# electronicload.net
KiCad netlist of a schematic drawn in EAGLE
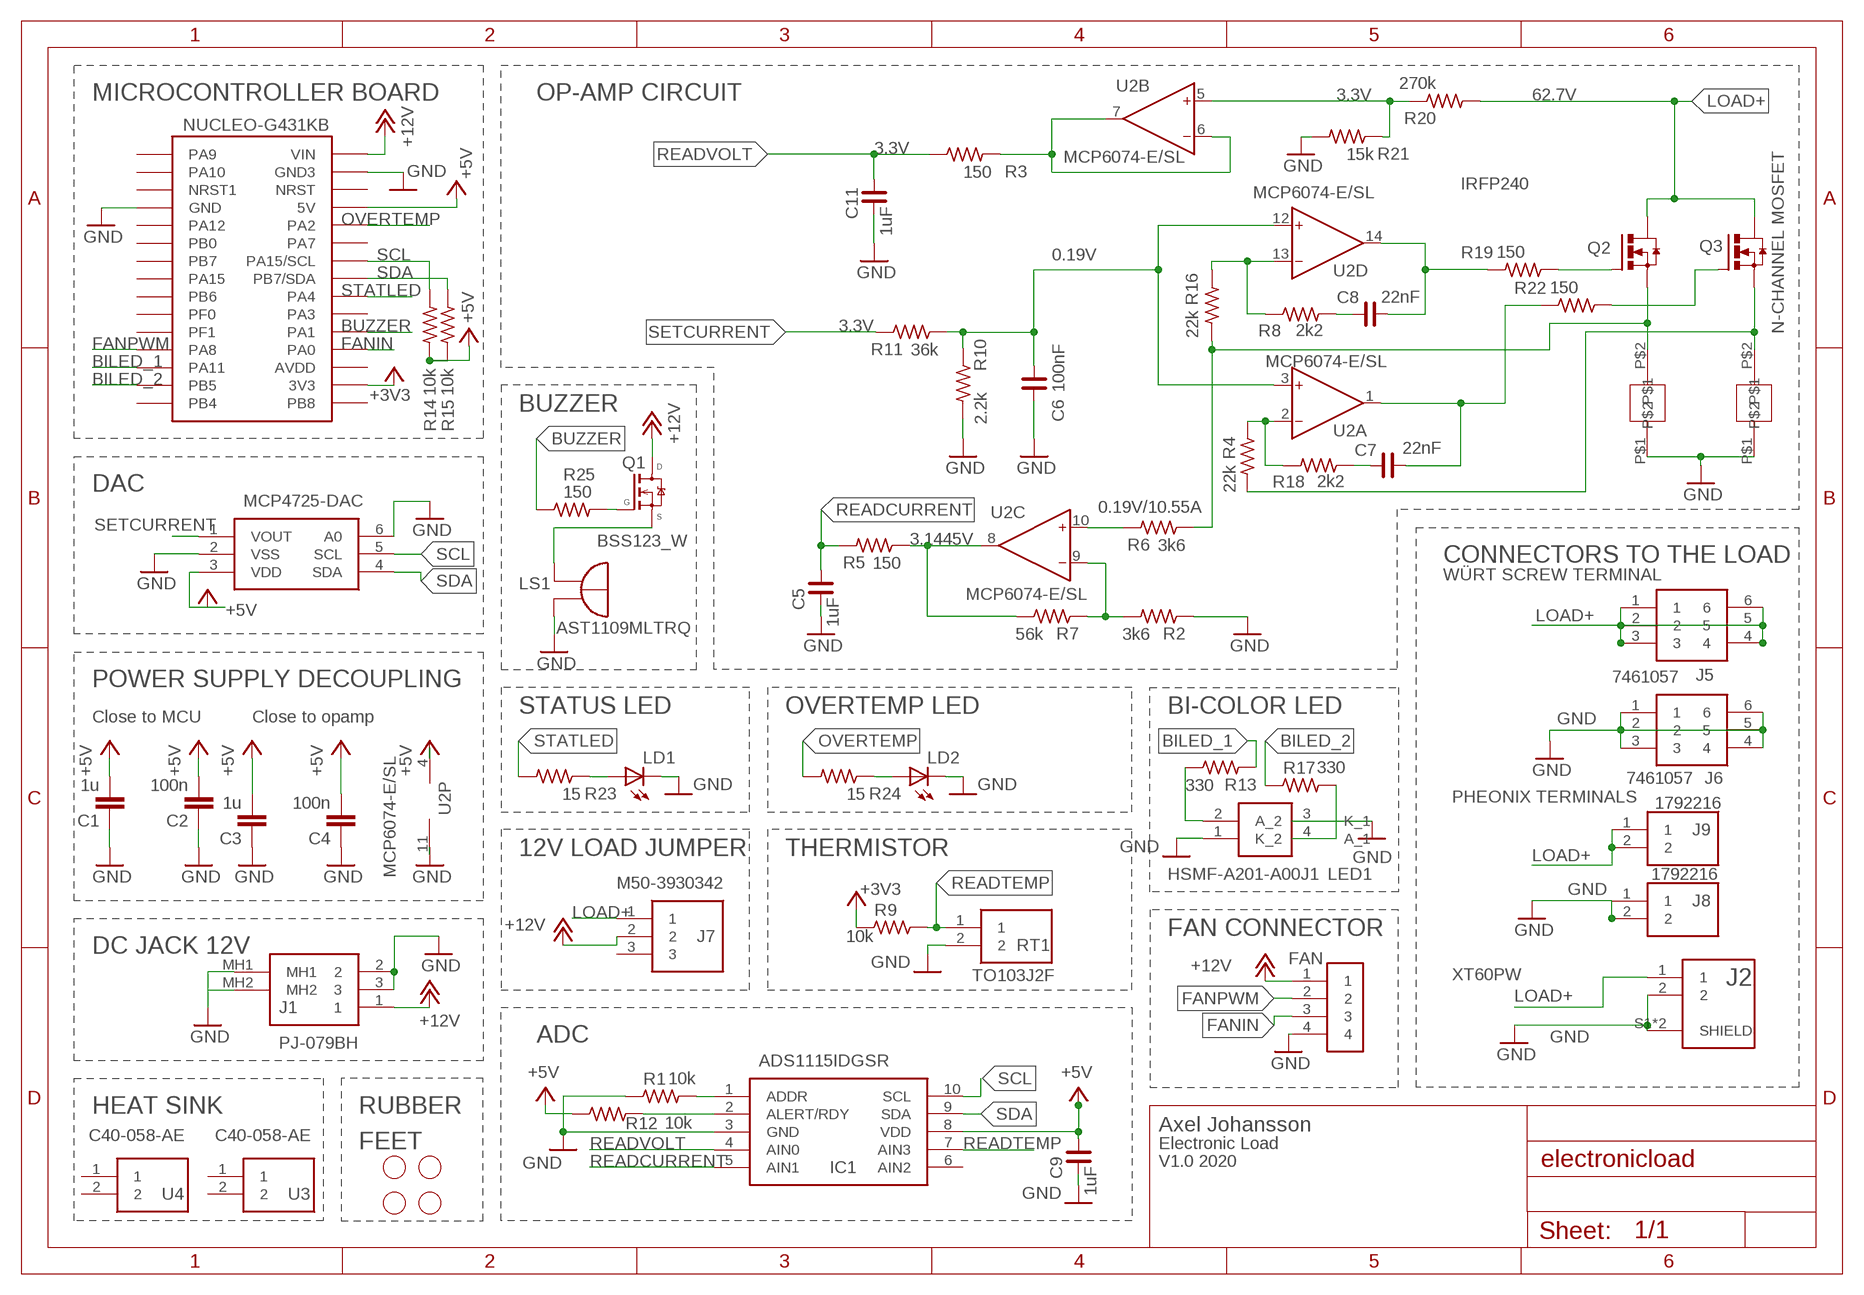
[diagram p0: schematic, sheet 1]

(export (version "E")
  (design (tool "Eeschema 10.0.6"))
  (components
    (comp (ref "C1")
      (value "1u")
      (footprint "eagle-import:C0603K")
      (fields (field (name "TOLERANCE") "10%") (field (name "VOLTAGE") "16V"))
      (libsource (lib "eagle-import") (part "C-EUC0603K"))
    )
    (comp (ref "C2")
      (value "100n")
      (footprint "eagle-import:C0603K")
      (fields (field (name "TOLERANCE") "10%") (field (name "VOLTAGE") "50V"))
      (libsource (lib "eagle-import") (part "C-EUC0603K"))
    )
    (comp (ref "C3")
      (value "1u")
      (footprint "eagle-import:C0603K")
      (fields (field (name "TOLERANCE") "10%") (field (name "VOLTAGE") "16V"))
      (libsource (lib "eagle-import") (part "C-EUC0603K"))
    )
    (comp (ref "C4")
      (value "100n")
      (footprint "eagle-import:C0603K")
      (fields (field (name "TOLERANCE") "10%") (field (name "VOLTAGE") "50V"))
      (libsource (lib "eagle-import") (part "C-EUC0603K"))
    )
    (comp (ref "C5")
      (value "1uF")
      (footprint "eagle-import:C0805")
      (libsource (lib "eagle-import") (part "C_0805"))
    )
    (comp (ref "C6")
      (value "100nF")
      (footprint "eagle-import:C0805")
      (libsource (lib "eagle-import") (part "C_0805"))
    )
    (comp (ref "C7")
      (value "22nF")
      (footprint "eagle-import:C0805")
      (libsource (lib "eagle-import") (part "C_0805"))
    )
    (comp (ref "C8")
      (value "22nF")
      (footprint "eagle-import:C0805")
      (libsource (lib "eagle-import") (part "C_0805"))
    )
    (comp (ref "C9")
      (value "1uF")
      (footprint "eagle-import:C0805")
      (libsource (lib "eagle-import") (part "C_0805"))
    )
    (comp (ref "C11")
      (value "1uF")
      (footprint "eagle-import:C0805")
      (libsource (lib "eagle-import") (part "C_0805"))
    )
    (comp (ref "FAN")
      (value "B4B-PH-K-S(LF)(SN)")
      (footprint "eagle-import:JST_B4B-PH-K-S(LF)(SN)")
      (fields (field (name "MF") "JST Sales"))
      (libsource (lib "eagle-import") (part "B4B-PH-K-S(LF)(SN)"))
    )
    (comp (ref "IC1")
      (value "ADS1115IDGSR")
      (footprint "eagle-import:SOP50P490X110-10N")
      (fields (field (name "MOUSER_PART_NUMBER") "595-ADS1115IDGSR"))
      (libsource (lib "eagle-import") (part "ADS1115IDGSR"))
    )
    (comp (ref "J1")
      (value "PJ-079BH")
      (footprint "eagle-import:PJ079BH")
      (fields (field (name "MOUSER_PART_NUMBER") "490-PJ-079BH"))
      (libsource (lib "eagle-import") (part "PJ-079BH"))
    )
    (comp (ref "J2")
      (value "XT60PW-F")
      (footprint "eagle-import:AMASS_XT60PW-F")
      (fields (field (name "MF") "AMASS"))
      (libsource (lib "eagle-import") (part "XT60PW-F"))
    )
    (comp (ref "J5")
      (value "7461057")
      (footprint "eagle-import:7461057")
      (fields (field (name "MOUSER_PART_NUMBER") "710-7461057"))
      (libsource (lib "eagle-import") (part "7461057"))
    )
    (comp (ref "J6")
      (value "7461057")
      (footprint "eagle-import:7461057")
      (fields (field (name "MOUSER_PART_NUMBER") "710-7461057"))
      (libsource (lib "eagle-import") (part "7461057"))
    )
    (comp (ref "J7")
      (value "M50-3930342")
      (footprint "eagle-import:M503930342")
      (fields (field (name "MOUSER_PART_NUMBER") "855-M50-3930342"))
      (libsource (lib "eagle-import") (part "M50-3930342"))
    )
    (comp (ref "J8")
      (value "1792216")
      (footprint "eagle-import:1792216")
      (fields (field (name "MOUSER_PART_NUMBER") "651-1792216"))
      (libsource (lib "eagle-import") (part "1792216"))
    )
    (comp (ref "J9")
      (value "1792216")
      (footprint "eagle-import:1792216")
      (fields (field (name "MOUSER_PART_NUMBER") "651-1792216"))
      (libsource (lib "eagle-import") (part "1792216"))
    )
    (comp (ref "LD1")
      (value "LEDCHIP-LED0805")
      (footprint "eagle-import:CHIP-LED0805")
      (libsource (lib "eagle-import") (part "LEDCHIP-LED0805"))
    )
    (comp (ref "LD2")
      (value "LEDCHIP-LED0805")
      (footprint "eagle-import:CHIP-LED0805")
      (libsource (lib "eagle-import") (part "LEDCHIP-LED0805"))
    )
    (comp (ref "LED1")
      (value "HSMF-A201-A00J1")
      (footprint "eagle-import:AVAGO_PLCC4")
      (fields (field (name "MOUSER_PART_NUMBER") "630-HSMF-A201-A00J1"))
      (libsource (lib "eagle-import") (part "HSMF-A201-A00J1"))
    )
    (comp (ref "LS1")
      (value "AST1109MLTRQ")
      (footprint "eagle-import:XDCR_AST1109MLTRQ")
      (fields (field (name "DIGI-KEY_PART_NUMBER") "458-1093-1-ND") (field (name "MF") "Mallory Sonalert"))
      (libsource (lib "eagle-import") (part "AST1109MLTRQ"))
    )
    (comp (ref "MCP4725-DAC")
      (value "MCP4725A0T-E_CH")
      (footprint "eagle-import:SOT95P270X145-6N")
      (fields
        (field (name "MANUFACTURER_PART_NUMBER") "MCP4725A0T-E/CH")
        (field (name "MOUSER_PART_NUMBER") "579-MCP4725A0TECH")
      )
      (libsource (lib "eagle-import") (part "MCP4725A0T-E_CH"))
    )
    (comp (ref "Q1")
      (value "BSS123_W")
      (footprint "eagle-import:SOT23_GSD_W")
      (libsource (lib "eagle-import") (part "BSS123_W"))
    )
    (comp (ref "Q2")
      (value "IRFP240")
      (footprint "eagle-import:TO247AC")
      (fields (field (name "MF") "Vishay Siliconix"))
      (libsource (lib "eagle-import") (part "IRFP240"))
    )
    (comp (ref "Q3")
      (value "IRFP240")
      (footprint "eagle-import:TO247AC")
      (fields (field (name "MF") "Vishay Siliconix"))
      (libsource (lib "eagle-import") (part "IRFP240"))
    )
    (comp (ref "R1")
      (value "10k")
      (footprint "eagle-import:R0805")
      (libsource (lib "eagle-import") (part "R_0805"))
    )
    (comp (ref "R2")
      (value "3k6")
      (footprint "eagle-import:R0805")
      (libsource (lib "eagle-import") (part "R_0805"))
    )
    (comp (ref "R3")
      (value "150")
      (footprint "eagle-import:R0805")
      (libsource (lib "eagle-import") (part "R_0805"))
    )
    (comp (ref "R4")
      (value "22k")
      (footprint "eagle-import:R0805")
      (libsource (lib "eagle-import") (part "R_0805"))
    )
    (comp (ref "R5")
      (value "150")
      (footprint "eagle-import:R0805")
      (libsource (lib "eagle-import") (part "R_0805"))
    )
    (comp (ref "R6")
      (value "3k6")
      (footprint "eagle-import:R0805")
      (libsource (lib "eagle-import") (part "R_0805"))
    )
    (comp (ref "R7")
      (value "56k")
      (footprint "eagle-import:R0805")
      (libsource (lib "eagle-import") (part "R_0805"))
    )
    (comp (ref "R8")
      (value "2k2")
      (footprint "eagle-import:R0805")
      (libsource (lib "eagle-import") (part "R_0805"))
    )
    (comp (ref "R9")
      (value "10k")
      (footprint "eagle-import:R0805")
      (libsource (lib "eagle-import") (part "R_0805"))
    )
    (comp (ref "R10")
      (value "2.2k")
      (footprint "eagle-import:R0805")
      (libsource (lib "eagle-import") (part "R_0805"))
    )
    (comp (ref "R11")
      (value "36k")
      (footprint "eagle-import:R0805")
      (libsource (lib "eagle-import") (part "R_0805"))
    )
    (comp (ref "R12")
      (value "10k")
      (footprint "eagle-import:R0805")
      (libsource (lib "eagle-import") (part "R_0805"))
    )
    (comp (ref "R13")
      (value "330")
      (footprint "eagle-import:R0805")
      (libsource (lib "eagle-import") (part "R_0805"))
    )
    (comp (ref "R14")
      (value "10k")
      (footprint "eagle-import:R0805")
      (libsource (lib "eagle-import") (part "R_0805"))
    )
    (comp (ref "R15")
      (value "10k")
      (footprint "eagle-import:R0805")
      (libsource (lib "eagle-import") (part "R_0805"))
    )
    (comp (ref "R16")
      (value "22k")
      (footprint "eagle-import:R0805")
      (libsource (lib "eagle-import") (part "R_0805"))
    )
    (comp (ref "R17")
      (value "330")
      (footprint "eagle-import:R0805")
      (libsource (lib "eagle-import") (part "R_0805"))
    )
    (comp (ref "R18")
      (value "2k2")
      (footprint "eagle-import:R0805")
      (libsource (lib "eagle-import") (part "R_0805"))
    )
    (comp (ref "R19")
      (value "150")
      (footprint "eagle-import:R0805")
      (libsource (lib "eagle-import") (part "R_0805"))
    )
    (comp (ref "R20")
      (value "270k")
      (footprint "eagle-import:R0805")
      (libsource (lib "eagle-import") (part "R_0805"))
    )
    (comp (ref "R21")
      (value "15k")
      (footprint "eagle-import:R0805")
      (libsource (lib "eagle-import") (part "R_0805"))
    )
    (comp (ref "R22")
      (value "150")
      (footprint "eagle-import:R0805")
      (libsource (lib "eagle-import") (part "R_0805"))
    )
    (comp (ref "R23")
      (value "15")
      (footprint "eagle-import:R0805")
      (libsource (lib "eagle-import") (part "R_0805"))
    )
    (comp (ref "R24")
      (value "15")
      (footprint "eagle-import:R0805")
      (libsource (lib "eagle-import") (part "R_0805"))
    )
    (comp (ref "R25")
      (value "150")
      (footprint "eagle-import:R0805")
      (libsource (lib "eagle-import") (part "R_0805"))
    )
    (comp (ref "RT1")
      (value "TO103J2F")
      (footprint "eagle-import:TO508P483X1016X2337-2P")
      (fields (field (name "MOUSER_PART_NUMBER") "803-TO103J2F"))
      (libsource (lib "eagle-import") (part "TO103J2F"))
    )
    (comp (ref "U$1")
      (value "NANO")
      (footprint "eagle-import:NANO")
      (libsource (lib "eagle-import") (part "NANO"))
    )
    (comp (ref "U$2")
      (value "RUBBER_FEET")
      (footprint "eagle-import:RUBBER_FEET")
      (libsource (lib "eagle-import") (part "RUBBER_FEET"))
    )
    (comp (ref "U$3")
      (value "CURRENTSENSE_RESISTOR_SMD2817")
      (footprint "eagle-import:CURRENTSENSE_RESISTOR_SMD2817")
      (libsource (lib "eagle-import") (part "CURRENTSENSE_RESISTOR_SMD2817"))
    )
    (comp (ref "U$4")
      (value "CURRENTSENSE_RESISTOR_SMD2817")
      (footprint "eagle-import:CURRENTSENSE_RESISTOR_SMD2817")
      (libsource (lib "eagle-import") (part "CURRENTSENSE_RESISTOR_SMD2817"))
    )
    (comp (ref "U$5")
      (value "RUBBER_FEET")
      (footprint "eagle-import:RUBBER_FEET")
      (libsource (lib "eagle-import") (part "RUBBER_FEET"))
    )
    (comp (ref "U$6")
      (value "RUBBER_FEET")
      (footprint "eagle-import:RUBBER_FEET")
      (libsource (lib "eagle-import") (part "RUBBER_FEET"))
    )
    (comp (ref "U$7")
      (value "RUBBER_FEET")
      (footprint "eagle-import:RUBBER_FEET")
      (libsource (lib "eagle-import") (part "RUBBER_FEET"))
    )
    (comp (ref "U2")
      (value "MCP6074-E/SL")
      (footprint "eagle-import:SO14")
      (libsource (lib "eagle-import") (part "AD8608R"))
    )
    (comp (ref "U3")
      (value "C40-058-AE")
      (footprint "eagle-import:C40058AE")
      (fields (field (name "MOUSER_PART_NUMBER") "588-C40-058-AE"))
      (libsource (lib "eagle-import") (part "C40-058-AE"))
    )
    (comp (ref "U4")
      (value "C40-058-AE")
      (footprint "eagle-import:C40058AE")
      (fields (field (name "MOUSER_PART_NUMBER") "588-C40-058-AE"))
      (libsource (lib "eagle-import") (part "C40-058-AE"))
    )
  )
  (nets
    (net (code "1") (name "+3V3") (class "Default")
      (node (ref "R9") (pin "1") (pinfunction "1_1") (pintype "passive"))
      (node (ref "U$1") (pin "RX1") (pinfunction "3V3_RX1") (pintype "bidirectional"))
    )
    (net (code "2") (name "+5V") (class "Default")
      (node (ref "C1") (pin "2") (pinfunction "2_2") (pintype "passive"))
      (node (ref "C2") (pin "2") (pinfunction "2_2") (pintype "passive"))
      (node (ref "C3") (pin "2") (pinfunction "2_2") (pintype "passive"))
      (node (ref "C4") (pin "2") (pinfunction "2_2") (pintype "passive"))
      (node (ref "C9") (pin "2") (pinfunction "2_2") (pintype "passive"))
      (node (ref "IC1") (pin "8") (pinfunction "VDD_8") (pintype "bidirectional"))
      (node (ref "MCP4725-DAC") (pin "3") (pinfunction "VDD_3") (pintype "bidirectional"))
      (node (ref "R12") (pin "1") (pinfunction "1_1") (pintype "passive"))
      (node (ref "R14") (pin "1") (pinfunction "1_1") (pintype "passive"))
      (node (ref "R15") (pin "1") (pinfunction "1_1") (pintype "passive"))
      (node (ref "U$1") (pin "D9") (pinfunction "5V_D9") (pintype "bidirectional"))
      (node (ref "U2") (pin "4") (pinfunction "V+_4") (pintype "power_in"))
    )
    (net (code "3") (name "+12V") (class "Default")
      (node (ref "FAN") (pin "1") (pinfunction "1_1") (pintype "passive"))
      (node (ref "J1") (pin "1") (pinfunction "1_1") (pintype "bidirectional"))
      (node (ref "J7") (pin "2") (pinfunction "2_2") (pintype "bidirectional"))
      (node (ref "Q1") (pin "D") (pinfunction "D_D") (pintype "passive"))
      (node (ref "U$1") (pin "D12") (pinfunction "VIN_D12") (pintype "bidirectional"))
    )
    (net (code "4") (name "BILED_1") (class "Default")
      (node (ref "R13") (pin "1") (pinfunction "1_1") (pintype "passive"))
      (node (ref "U$1") (pin "RST") (pinfunction "PA11_RST") (pintype "bidirectional"))
    )
    (net (code "5") (name "BILED_2") (class "Default")
      (node (ref "R17") (pin "1") (pinfunction "1_1") (pintype "passive"))
      (node (ref "U$1") (pin "GND") (pinfunction "PB5_GND") (pintype "bidirectional"))
    )
    (net (code "6") (name "BUZZER") (class "Default")
      (node (ref "R25") (pin "1") (pinfunction "1_1") (pintype "passive"))
      (node (ref "U$1") (pin "D2") (pinfunction "PA1_D2") (pintype "bidirectional"))
    )
    (net (code "7") (name "FANIN") (class "Default")
      (node (ref "FAN") (pin "3") (pinfunction "3_3") (pintype "passive"))
      (node (ref "U$1") (pin "GND1") (pinfunction "PA0_GND1") (pintype "bidirectional"))
    )
    (net (code "8") (name "FANPWM") (class "Default")
      (node (ref "FAN") (pin "2") (pinfunction "2_2") (pintype "passive"))
      (node (ref "U$1") (pin "5V") (pinfunction "PA8_5V") (pintype "bidirectional"))
    )
    (net (code "9") (name "GND") (class "Default")
      (node (ref "C1") (pin "1") (pinfunction "1_1") (pintype "passive"))
      (node (ref "C11") (pin "1") (pinfunction "1_1") (pintype "passive"))
      (node (ref "C2") (pin "1") (pinfunction "1_1") (pintype "passive"))
      (node (ref "C3") (pin "1") (pinfunction "1_1") (pintype "passive"))
      (node (ref "C4") (pin "1") (pinfunction "1_1") (pintype "passive"))
      (node (ref "C5") (pin "1") (pinfunction "1_1") (pintype "passive"))
      (node (ref "C6") (pin "1") (pinfunction "1_1") (pintype "passive"))
      (node (ref "C9") (pin "1") (pinfunction "1_1") (pintype "passive"))
      (node (ref "FAN") (pin "4") (pinfunction "4_4") (pintype "passive"))
      (node (ref "IC1") (pin "3") (pinfunction "GND_3") (pintype "bidirectional"))
      (node (ref "J1") (pin "2") (pinfunction "2_2") (pintype "bidirectional"))
      (node (ref "J1") (pin "3") (pinfunction "3_3") (pintype "bidirectional"))
      (node (ref "J1") (pin "MH1") (pinfunction "MH1_MH1") (pintype "bidirectional"))
      (node (ref "J1") (pin "MH2") (pinfunction "MH2_MH2") (pintype "bidirectional"))
      (node (ref "J2") (pin "2") (pinfunction "2_2") (pintype "passive"))
      (node (ref "J2") (pin "S1") (pinfunction "SHIELD_S1") (pintype "passive"))
      (node (ref "J2") (pin "S2") (pinfunction "SHIELD_S2") (pintype "passive"))
      (node (ref "J6") (pin "1") (pinfunction "1_1") (pintype "bidirectional"))
      (node (ref "J6") (pin "2") (pinfunction "2_2") (pintype "bidirectional"))
      (node (ref "J6") (pin "3") (pinfunction "3_3") (pintype "bidirectional"))
      (node (ref "J6") (pin "4") (pinfunction "4_4") (pintype "bidirectional"))
      (node (ref "J6") (pin "5") (pinfunction "5_5") (pintype "bidirectional"))
      (node (ref "J6") (pin "6") (pinfunction "6_6") (pintype "bidirectional"))
      (node (ref "J8") (pin "1") (pinfunction "1_1") (pintype "bidirectional"))
      (node (ref "J8") (pin "2") (pinfunction "2_2") (pintype "bidirectional"))
      (node (ref "LD1") (pin "C") (pinfunction "C_C") (pintype "passive"))
      (node (ref "LD2") (pin "C") (pinfunction "C_C") (pintype "passive"))
      (node (ref "LED1") (pin "1") (pinfunction "K_2_1") (pintype "bidirectional"))
      (node (ref "LED1") (pin "3") (pinfunction "K_1_3") (pintype "bidirectional"))
      (node (ref "LS1") (pin "2") (pinfunction "2_2") (pintype "passive"))
      (node (ref "MCP4725-DAC") (pin "2") (pinfunction "VSS_2") (pintype "bidirectional"))
      (node (ref "MCP4725-DAC") (pin "6") (pinfunction "A0_6") (pintype "bidirectional"))
      (node (ref "R1") (pin "1") (pinfunction "1_1") (pintype "passive"))
      (node (ref "R10") (pin "2") (pinfunction "2_2") (pintype "passive"))
      (node (ref "R2") (pin "1") (pinfunction "1_1") (pintype "passive"))
      (node (ref "R21") (pin "2") (pinfunction "2_2") (pintype "passive"))
      (node (ref "RT1") (pin "2") (pinfunction "2_2") (pintype "bidirectional"))
      (node (ref "U$1") (pin "A0") (pinfunction "GND_A0") (pintype "bidirectional"))
      (node (ref "U$1") (pin "D11") (pinfunction "GND3_D11") (pintype "bidirectional"))
      (node (ref "U$3") (pin "P$1") (pinfunction "P$1_P$1") (pintype "bidirectional"))
      (node (ref "U$4") (pin "P$1") (pinfunction "P$1_P$1") (pintype "bidirectional"))
      (node (ref "U2") (pin "11") (pinfunction "V-_11") (pintype "power_in"))
    )
    (net (code "10") (name "LOAD+") (class "Default")
      (node (ref "J2") (pin "1") (pinfunction "1_1") (pintype "passive"))
      (node (ref "J5") (pin "1") (pinfunction "1_1") (pintype "bidirectional"))
      (node (ref "J5") (pin "2") (pinfunction "2_2") (pintype "bidirectional"))
      (node (ref "J5") (pin "3") (pinfunction "3_3") (pintype "bidirectional"))
      (node (ref "J5") (pin "4") (pinfunction "4_4") (pintype "bidirectional"))
      (node (ref "J5") (pin "5") (pinfunction "5_5") (pintype "bidirectional"))
      (node (ref "J5") (pin "6") (pinfunction "6_6") (pintype "bidirectional"))
      (node (ref "J7") (pin "1") (pinfunction "1_1") (pintype "bidirectional"))
      (node (ref "J9") (pin "1") (pinfunction "1_1") (pintype "bidirectional"))
      (node (ref "J9") (pin "2") (pinfunction "2_2") (pintype "bidirectional"))
      (node (ref "Q2") (pin "2") (pinfunction "D_2") (pintype "passive"))
      (node (ref "Q3") (pin "2") (pinfunction "D_2") (pintype "passive"))
      (node (ref "R20") (pin "1") (pinfunction "1_1") (pintype "passive"))
    )
    (net (code "11") (name "Net-(C7-Pad2)") (class "Default")
      (node (ref "C7") (pin "2") (pinfunction "2_2") (pintype "passive"))
      (node (ref "R18") (pin "2") (pinfunction "2_2") (pintype "passive"))
    )
    (net (code "12") (name "Net-(C8-Pad2)") (class "Default")
      (node (ref "C8") (pin "2") (pinfunction "2_2") (pintype "passive"))
      (node (ref "R8") (pin "2") (pinfunction "2_2") (pintype "passive"))
    )
    (net (code "13") (name "Net-(IC1-ADDR)") (class "Default")
      (node (ref "IC1") (pin "1") (pinfunction "ADDR_1") (pintype "bidirectional"))
      (node (ref "R1") (pin "2") (pinfunction "2_2") (pintype "passive"))
    )
    (net (code "14") (name "Net-(IC1-ALERT{slash}RDY)") (class "Default")
      (node (ref "IC1") (pin "2") (pinfunction "ALERT/RDY_2") (pintype "bidirectional"))
      (node (ref "R12") (pin "2") (pinfunction "2_2") (pintype "passive"))
    )
    (net (code "15") (name "Net-(LD1-PadA)") (class "Default")
      (node (ref "LD1") (pin "A") (pinfunction "A_A") (pintype "passive"))
      (node (ref "R23") (pin "1") (pinfunction "1_1") (pintype "passive"))
    )
    (net (code "16") (name "Net-(LD2-PadA)") (class "Default")
      (node (ref "LD2") (pin "A") (pinfunction "A_A") (pintype "passive"))
      (node (ref "R24") (pin "1") (pinfunction "1_1") (pintype "passive"))
    )
    (net (code "17") (name "Net-(LED1-A_1)") (class "Default")
      (node (ref "LED1") (pin "4") (pinfunction "A_1_4") (pintype "bidirectional"))
      (node (ref "R17") (pin "2") (pinfunction "2_2") (pintype "passive"))
    )
    (net (code "18") (name "Net-(LED1-A_2)") (class "Default")
      (node (ref "LED1") (pin "2") (pinfunction "A_2_2") (pintype "bidirectional"))
      (node (ref "R13") (pin "2") (pinfunction "2_2") (pintype "passive"))
    )
    (net (code "19") (name "Net-(LS1-Pad1)") (class "Default")
      (node (ref "LS1") (pin "1") (pinfunction "1_1") (pintype "passive"))
      (node (ref "Q1") (pin "S") (pinfunction "S_S") (pintype "passive"))
    )
    (net (code "20") (name "Net-(Q1-PadG)") (class "Default")
      (node (ref "Q1") (pin "G") (pinfunction "G_G") (pintype "passive"))
      (node (ref "R25") (pin "2") (pinfunction "2_2") (pintype "passive"))
    )
    (net (code "21") (name "Net-(Q2-G)") (class "Default")
      (node (ref "Q2") (pin "1") (pinfunction "G_1") (pintype "passive"))
      (node (ref "R19") (pin "2") (pinfunction "2_2") (pintype "passive"))
    )
    (net (code "22") (name "Net-(Q2-S)") (class "Default")
      (node (ref "Q2") (pin "3") (pinfunction "S_3") (pintype "passive"))
      (node (ref "R16") (pin "2") (pinfunction "2_2") (pintype "passive"))
      (node (ref "R6") (pin "1") (pinfunction "1_1") (pintype "passive"))
      (node (ref "U$4") (pin "P$2") (pinfunction "P$2_P$2") (pintype "bidirectional"))
    )
    (net (code "23") (name "Net-(Q3-G)") (class "Default")
      (node (ref "Q3") (pin "1") (pinfunction "G_1") (pintype "passive"))
      (node (ref "R22") (pin "2") (pinfunction "2_2") (pintype "passive"))
    )
    (net (code "24") (name "Net-(Q3-S)") (class "Default")
      (node (ref "Q3") (pin "3") (pinfunction "S_3") (pintype "passive"))
      (node (ref "R4") (pin "2") (pinfunction "2_2") (pintype "passive"))
      (node (ref "U$3") (pin "P$2") (pinfunction "P$2_P$2") (pintype "bidirectional"))
    )
    (net (code "25") (name "Net-(U2A-IN+)") (class "Default")
      (node (ref "C6") (pin "2") (pinfunction "2_2") (pintype "passive"))
      (node (ref "R10") (pin "1") (pinfunction "1_1") (pintype "passive"))
      (node (ref "R11") (pin "1") (pinfunction "1_1") (pintype "passive"))
      (node (ref "U2") (pin "12") (pinfunction "IN+_12") (pintype "input"))
      (node (ref "U2") (pin "3") (pinfunction "IN+_3") (pintype "input"))
    )
    (net (code "26") (name "Net-(U2A-IN-)") (class "Default")
      (node (ref "R18") (pin "1") (pinfunction "1_1") (pintype "passive"))
      (node (ref "R4") (pin "1") (pinfunction "1_1") (pintype "passive"))
      (node (ref "U2") (pin "2") (pinfunction "IN-_2") (pintype "input"))
    )
    (net (code "27") (name "Net-(U2A-OUT)") (class "Default")
      (node (ref "C7") (pin "1") (pinfunction "1_1") (pintype "passive"))
      (node (ref "R22") (pin "1") (pinfunction "1_1") (pintype "passive"))
      (node (ref "U2") (pin "1") (pinfunction "OUT_1") (pintype "output"))
    )
    (net (code "28") (name "Net-(U2B-IN+)") (class "Default")
      (node (ref "R20") (pin "2") (pinfunction "2_2") (pintype "passive"))
      (node (ref "R21") (pin "1") (pinfunction "1_1") (pintype "passive"))
      (node (ref "U2") (pin "5") (pinfunction "IN+_5") (pintype "input"))
    )
    (net (code "29") (name "Net-(U2B-IN-)") (class "Default")
      (node (ref "R3") (pin "1") (pinfunction "1_1") (pintype "passive"))
      (node (ref "U2") (pin "6") (pinfunction "IN-_6") (pintype "input"))
      (node (ref "U2") (pin "7") (pinfunction "OUT_7") (pintype "output"))
    )
    (net (code "30") (name "Net-(U2C-IN+)") (class "Default")
      (node (ref "R6") (pin "2") (pinfunction "2_2") (pintype "passive"))
      (node (ref "U2") (pin "10") (pinfunction "IN+_10") (pintype "input"))
    )
    (net (code "31") (name "Net-(U2C-IN-)") (class "Default")
      (node (ref "R2") (pin "2") (pinfunction "2_2") (pintype "passive"))
      (node (ref "R7") (pin "1") (pinfunction "1_1") (pintype "passive"))
      (node (ref "U2") (pin "9") (pinfunction "IN-_9") (pintype "input"))
    )
    (net (code "32") (name "Net-(U2C-OUT)") (class "Default")
      (node (ref "R5") (pin "1") (pinfunction "1_1") (pintype "passive"))
      (node (ref "R7") (pin "2") (pinfunction "2_2") (pintype "passive"))
      (node (ref "U2") (pin "8") (pinfunction "OUT_8") (pintype "output"))
    )
    (net (code "33") (name "Net-(U2D-IN-)") (class "Default")
      (node (ref "R16") (pin "1") (pinfunction "1_1") (pintype "passive"))
      (node (ref "R8") (pin "1") (pinfunction "1_1") (pintype "passive"))
      (node (ref "U2") (pin "13") (pinfunction "IN-_13") (pintype "input"))
    )
    (net (code "34") (name "Net-(U2D-OUT)") (class "Default")
      (node (ref "C8") (pin "1") (pinfunction "1_1") (pintype "passive"))
      (node (ref "R19") (pin "1") (pinfunction "1_1") (pintype "passive"))
      (node (ref "U2") (pin "14") (pinfunction "OUT_14") (pintype "output"))
    )
    (net (code "35") (name "OVERTEMP") (class "Default")
      (node (ref "R24") (pin "2") (pinfunction "2_2") (pintype "passive"))
      (node (ref "U$1") (pin "D8") (pinfunction "PA2_D8") (pintype "bidirectional"))
    )
    (net (code "36") (name "READCURRENT") (class "Default")
      (node (ref "C5") (pin "2") (pinfunction "2_2") (pintype "passive"))
      (node (ref "IC1") (pin "5") (pinfunction "AIN1_5") (pintype "bidirectional"))
      (node (ref "R5") (pin "2") (pinfunction "2_2") (pintype "passive"))
    )
    (net (code "37") (name "READTEMP") (class "Default")
      (node (ref "IC1") (pin "7") (pinfunction "AIN3_7") (pintype "bidirectional"))
      (node (ref "R9") (pin "2") (pinfunction "2_2") (pintype "passive"))
      (node (ref "RT1") (pin "1") (pinfunction "1_1") (pintype "bidirectional"))
    )
    (net (code "38") (name "READVOLT") (class "Default")
      (node (ref "C11") (pin "2") (pinfunction "2_2") (pintype "passive"))
      (node (ref "IC1") (pin "4") (pinfunction "AIN0_4") (pintype "bidirectional"))
      (node (ref "R3") (pin "2") (pinfunction "2_2") (pintype "passive"))
    )
    (net (code "39") (name "SCL") (class "Default")
      (node (ref "IC1") (pin "10") (pinfunction "SCL_10") (pintype "bidirectional"))
      (node (ref "MCP4725-DAC") (pin "5") (pinfunction "SCL_5") (pintype "bidirectional"))
      (node (ref "R14") (pin "2") (pinfunction "2_2") (pintype "passive"))
      (node (ref "U$1") (pin "D6") (pinfunction "PA15/SCL_D6") (pintype "bidirectional"))
    )
    (net (code "40") (name "SDA") (class "Default")
      (node (ref "IC1") (pin "9") (pinfunction "SDA_9") (pintype "bidirectional"))
      (node (ref "MCP4725-DAC") (pin "4") (pinfunction "SDA_4") (pintype "bidirectional"))
      (node (ref "R15") (pin "2") (pinfunction "2_2") (pintype "passive"))
      (node (ref "U$1") (pin "D5") (pinfunction "PB7/SDA_D5") (pintype "bidirectional"))
    )
    (net (code "41") (name "SETCURRENT") (class "Default")
      (node (ref "MCP4725-DAC") (pin "1") (pinfunction "VOUT_1") (pintype "bidirectional"))
      (node (ref "R11") (pin "2") (pinfunction "2_2") (pintype "passive"))
    )
    (net (code "42") (name "STATLED") (class "Default")
      (node (ref "R23") (pin "2") (pinfunction "2_2") (pintype "passive"))
      (node (ref "U$1") (pin "D4") (pinfunction "PA4_D4") (pintype "bidirectional"))
    )
    (net (code "43") (name "unconnected-(IC1-AIN2-Pad6)") (class "Default")
      (node (ref "IC1") (pin "6") (pinfunction "AIN2_6") (pintype "bidirectional"))
    )
    (net (code "44") (name "unconnected-(J7-Pad3)") (class "Default")
      (node (ref "J7") (pin "3") (pinfunction "3_3") (pintype "bidirectional"))
    )
    (net (code "45") (name "unconnected-(U$1-AVDD-PadRST1)") (class "Default")
      (node (ref "U$1") (pin "RST1") (pinfunction "AVDD_RST1") (pintype "bidirectional"))
    )
    (net (code "46") (name "unconnected-(U$1-NRST-PadD10)") (class "Default")
      (node (ref "U$1") (pin "D10") (pinfunction "NRST_D10") (pintype "bidirectional"))
    )
    (net (code "47") (name "unconnected-(U$1-NRST1-PadAREF)") (class "Default")
      (node (ref "U$1") (pin "AREF") (pinfunction "NRST1_AREF") (pintype "bidirectional"))
    )
    (net (code "48") (name "unconnected-(U$1-PA3-PadD3)") (class "Default")
      (node (ref "U$1") (pin "D3") (pinfunction "PA3_D3") (pintype "bidirectional"))
    )
    (net (code "49") (name "unconnected-(U$1-PA7-PadD7)") (class "Default")
      (node (ref "U$1") (pin "D7") (pinfunction "PA7_D7") (pintype "bidirectional"))
    )
    (net (code "50") (name "unconnected-(U$1-PA9-PadD13)") (class "Default")
      (node (ref "U$1") (pin "D13") (pinfunction "PA9_D13") (pintype "bidirectional"))
    )
    (net (code "51") (name "unconnected-(U$1-PA10-Pad3.3V)") (class "Default")
      (node (ref "U$1") (pin "3.3V") (pinfunction "PA10_3.3V") (pintype "bidirectional"))
    )
    (net (code "52") (name "unconnected-(U$1-PA12-PadA1)") (class "Default")
      (node (ref "U$1") (pin "A1") (pinfunction "PA12_A1") (pintype "bidirectional"))
    )
    (net (code "53") (name "unconnected-(U$1-PA15-PadA4)") (class "Default")
      (node (ref "U$1") (pin "A4") (pinfunction "PA15_A4") (pintype "bidirectional"))
    )
    (net (code "54") (name "unconnected-(U$1-PB0-PadA2)") (class "Default")
      (node (ref "U$1") (pin "A2") (pinfunction "PB0_A2") (pintype "bidirectional"))
    )
    (net (code "55") (name "unconnected-(U$1-PB4-PadRAW)") (class "Default")
      (node (ref "U$1") (pin "RAW") (pinfunction "PB4_RAW") (pintype "bidirectional"))
    )
    (net (code "56") (name "unconnected-(U$1-PB6-PadA5)") (class "Default")
      (node (ref "U$1") (pin "A5") (pinfunction "PB6_A5") (pintype "bidirectional"))
    )
    (net (code "57") (name "unconnected-(U$1-PB7-PadA3)") (class "Default")
      (node (ref "U$1") (pin "A3") (pinfunction "PB7_A3") (pintype "bidirectional"))
    )
    (net (code "58") (name "unconnected-(U$1-PB8-PadTX0)") (class "Default")
      (node (ref "U$1") (pin "TX0") (pinfunction "PB8_TX0") (pintype "bidirectional"))
    )
    (net (code "59") (name "unconnected-(U$1-PF0-PadA6)") (class "Default")
      (node (ref "U$1") (pin "A6") (pinfunction "PF0_A6") (pintype "bidirectional"))
    )
    (net (code "60") (name "unconnected-(U$1-PF1-PadA7)") (class "Default")
      (node (ref "U$1") (pin "A7") (pinfunction "PF1_A7") (pintype "bidirectional"))
    )
    (net (code "61") (name "unconnected-(U3-Pad1)") (class "Default")
      (node (ref "U3") (pin "1") (pinfunction "1_1") (pintype "bidirectional"))
    )
    (net (code "62") (name "unconnected-(U3-Pad2)") (class "Default")
      (node (ref "U3") (pin "2") (pinfunction "2_2") (pintype "bidirectional"))
    )
    (net (code "63") (name "unconnected-(U4-Pad1)") (class "Default")
      (node (ref "U4") (pin "1") (pinfunction "1_1") (pintype "bidirectional"))
    )
    (net (code "64") (name "unconnected-(U4-Pad2)") (class "Default")
      (node (ref "U4") (pin "2") (pinfunction "2_2") (pintype "bidirectional"))
    )
  )
)
